# 7segement4digits1badidea-max7219-smd-mk-.net
KiCad netlist of a schematic drawn in EAGLE
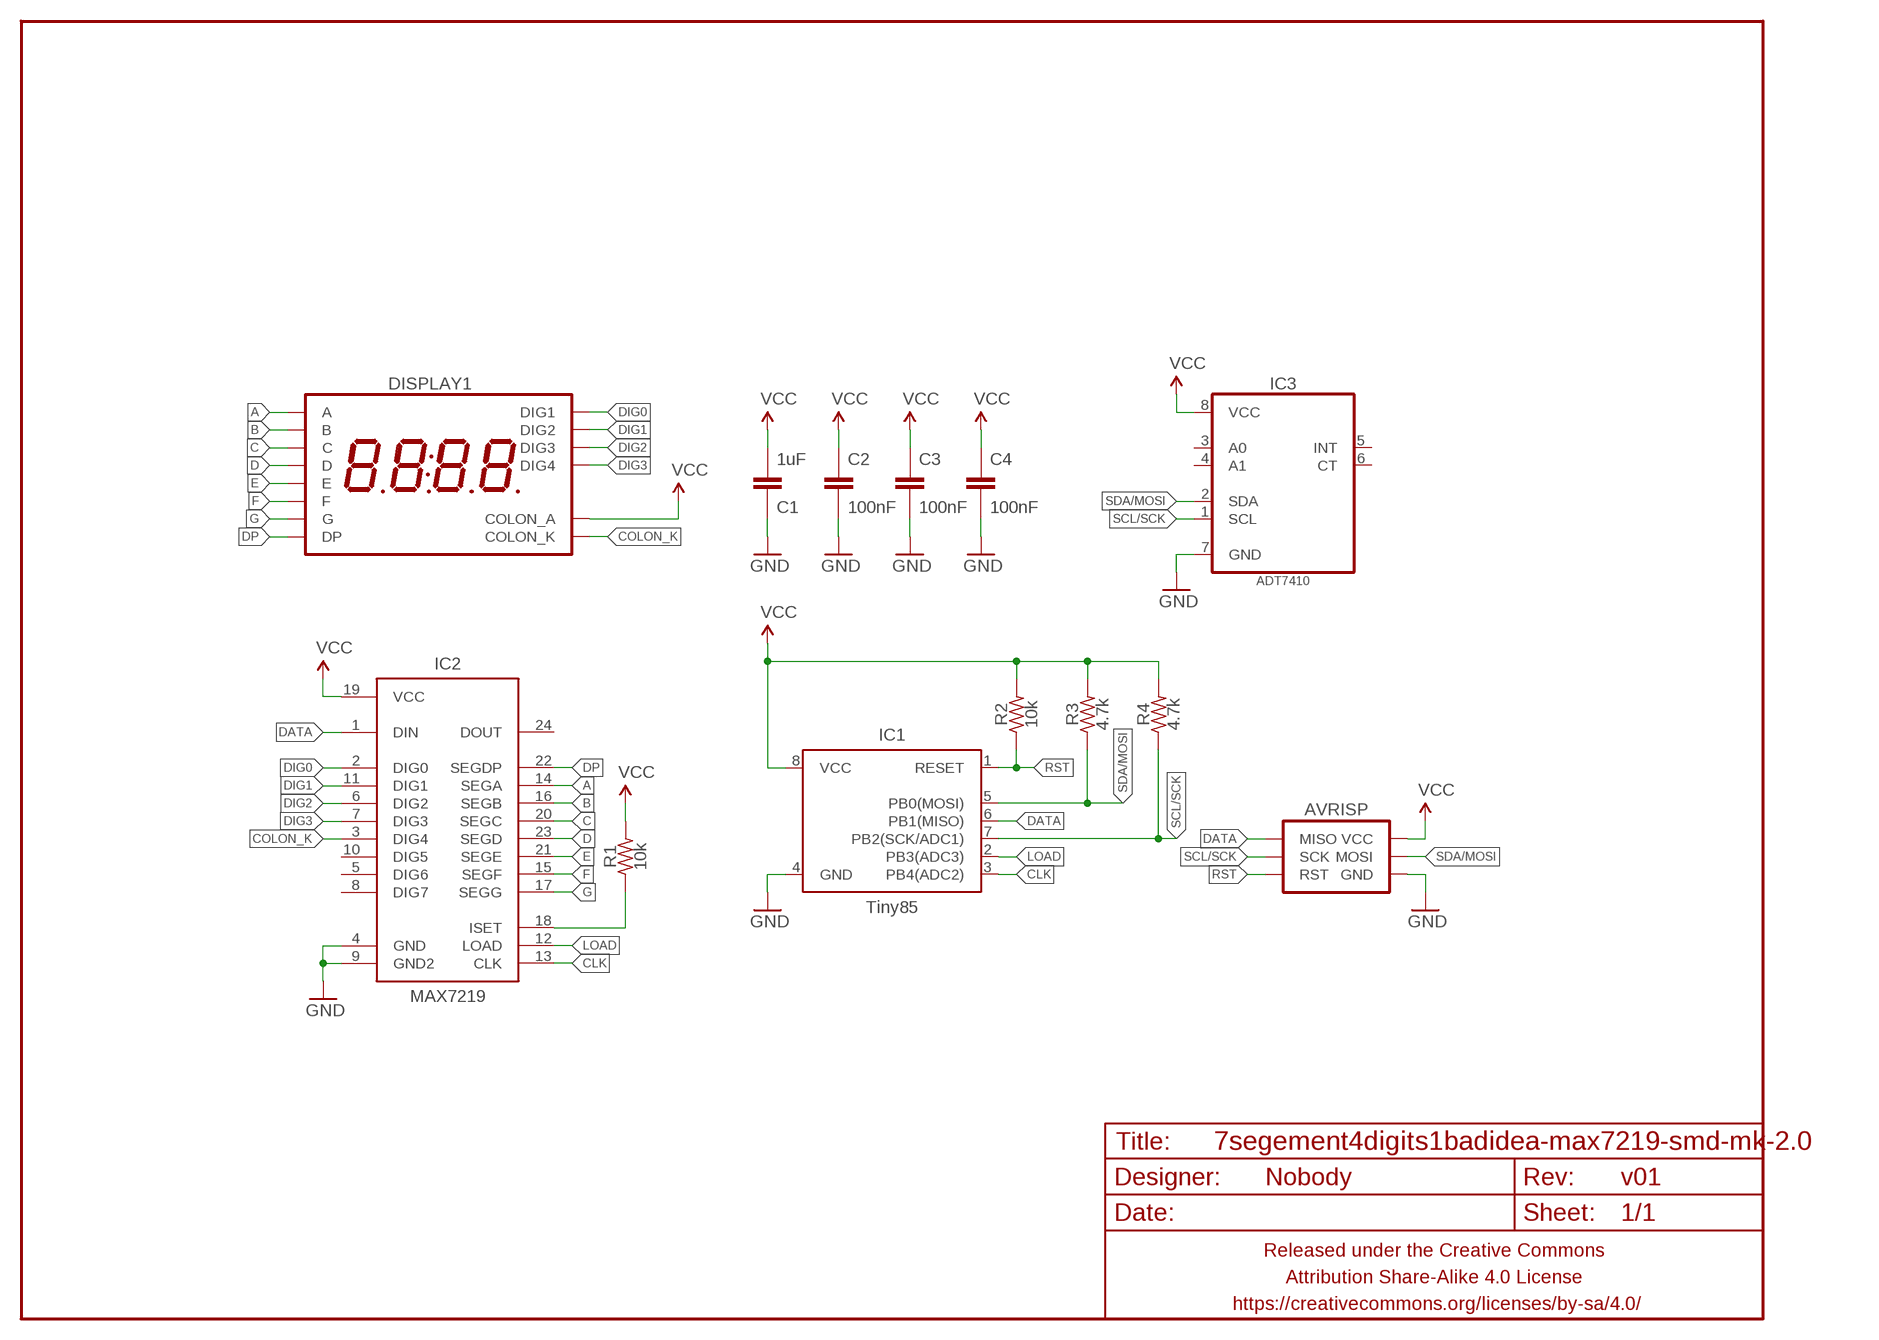
[diagram p0: schematic, sheet 1]

(export (version "E")
  (design (tool "Eeschema 10.0.6"))
  (components
    (comp (ref "AVRISP")
      (value "AVR_SPI_PRG_6PTH")
      (footprint "eagle-import:2X3")
      (libsource (lib "eagle-import") (part "AVR_SPI_PRG_6PTH"))
    )
    (comp (ref "C1")
      (value "1uF")
      (footprint "eagle-import:C0805")
      (libsource (lib "eagle-import") (part "CAPACITOR-CERAMICC0805"))
    )
    (comp (ref "C2")
      (value "100nF")
      (footprint "eagle-import:C0805")
      (libsource (lib "eagle-import") (part "CAPACITOR-CERAMICC0805"))
    )
    (comp (ref "C3")
      (value "100nF")
      (footprint "eagle-import:C0805")
      (libsource (lib "eagle-import") (part "CAPACITOR-CERAMICC0805"))
    )
    (comp (ref "C4")
      (value "100nF")
      (footprint "eagle-import:C0805")
      (libsource (lib "eagle-import") (part "CAPACITOR-CERAMICC0805"))
    )
    (comp (ref "DISPLAY1")
      (value "7SEG_4DIGIT_COLONADAFRUIT_0.56IN")
      (footprint "eagle-import:7SEG_4DIG")
      (libsource (lib "eagle-import") (part "7SEG_4DIGIT_COLONADAFRUIT_0.56IN"))
    )
    (comp (ref "FRAME1")
      (value "FRAME-LETTERNO_PACKAGE")
      (footprint "eagle-import:DUMMY")
      (fields (field (name "DESIGNER") "Nobody"))
      (libsource (lib "eagle-import") (part "FRAME-LETTERNO_PACKAGE"))
    )
    (comp (ref "IC1")
      (value "Tiny85")
      (footprint "eagle-import:SO08-EIAJ")
      (libsource (lib "eagle-import") (part "ATTINY45TINY85-20-SOICW"))
    )
    (comp (ref "IC2")
      (value "MAX7219")
      (footprint "eagle-import:SO24W")
      (libsource (lib "eagle-import") (part "MAX7219SOIC-W"))
    )
    (comp (ref "IC3")
      (value "ADT7410")
      (footprint "eagle-import:SOIC127P600X175-8N")
      (fields (field (name "MPN") "ADT7410TRZ"))
      (libsource (lib "eagle-import") (part "ADT7410TRZSOIC8N"))
    )
    (comp (ref "R1")
      (value "10k")
      (footprint "eagle-import:R0805")
      (libsource (lib "eagle-import") (part "RESISTORR0805"))
    )
    (comp (ref "R2")
      (value "10k")
      (footprint "eagle-import:R0805")
      (libsource (lib "eagle-import") (part "RESISTORR0805"))
    )
    (comp (ref "R3")
      (value "4.7k")
      (footprint "eagle-import:R0805")
      (libsource (lib "eagle-import") (part "RESISTORR0805"))
    )
    (comp (ref "R4")
      (value "4.7k")
      (footprint "eagle-import:R0805")
      (libsource (lib "eagle-import") (part "RESISTORR0805"))
    )
  )
  (nets
    (net (code "1") (name "A") (class "Default")
      (node (ref "DISPLAY1") (pin "P$13") (pinfunction "A_P$13") (pintype "passive"))
      (node (ref "IC2") (pin "14") (pinfunction "SEGA_14") (pintype "bidirectional"))
    )
    (net (code "2") (name "B") (class "Default")
      (node (ref "DISPLAY1") (pin "P$9") (pinfunction "B_P$9") (pintype "passive"))
      (node (ref "IC2") (pin "16") (pinfunction "SEGB_16") (pintype "bidirectional"))
    )
    (net (code "3") (name "C") (class "Default")
      (node (ref "DISPLAY1") (pin "P$4") (pinfunction "C_P$4") (pintype "passive"))
      (node (ref "IC2") (pin "20") (pinfunction "SEGC_20") (pintype "bidirectional"))
    )
    (net (code "4") (name "CLK") (class "Default")
      (node (ref "IC1") (pin "3") (pinfunction "PB4(ADC2)_3") (pintype "bidirectional"))
      (node (ref "IC2") (pin "13") (pinfunction "CLK_13") (pintype "bidirectional"))
    )
    (net (code "5") (name "COLON_K") (class "Default")
      (node (ref "DISPLAY1") (pin "P$7") (pinfunction "COLON_K_P$7") (pintype "passive"))
      (node (ref "IC2") (pin "3") (pinfunction "DIG4_3") (pintype "bidirectional"))
    )
    (net (code "6") (name "D") (class "Default")
      (node (ref "DISPLAY1") (pin "P$2") (pinfunction "D_P$2") (pintype "passive"))
      (node (ref "IC2") (pin "23") (pinfunction "SEGD_23") (pintype "bidirectional"))
    )
    (net (code "7") (name "DATA") (class "Default")
      (node (ref "AVRISP") (pin "1") (pinfunction "MISO_1") (pintype "passive"))
      (node (ref "IC1") (pin "6") (pinfunction "PB1(MISO)_6") (pintype "bidirectional"))
      (node (ref "IC2") (pin "1") (pinfunction "DIN_1") (pintype "bidirectional"))
    )
    (net (code "8") (name "DIG0") (class "Default")
      (node (ref "DISPLAY1") (pin "P$14") (pinfunction "DIG1_P$14") (pintype "passive"))
      (node (ref "IC2") (pin "2") (pinfunction "DIG0_2") (pintype "bidirectional"))
    )
    (net (code "9") (name "DIG1") (class "Default")
      (node (ref "DISPLAY1") (pin "P$11") (pinfunction "DIG2_P$11") (pintype "passive"))
      (node (ref "IC2") (pin "11") (pinfunction "DIG1_11") (pintype "bidirectional"))
    )
    (net (code "10") (name "DIG2") (class "Default")
      (node (ref "DISPLAY1") (pin "P$10") (pinfunction "DIG3_P$10") (pintype "passive"))
      (node (ref "IC2") (pin "6") (pinfunction "DIG2_6") (pintype "bidirectional"))
    )
    (net (code "11") (name "DIG3") (class "Default")
      (node (ref "DISPLAY1") (pin "P$6") (pinfunction "DIG4_P$6") (pintype "passive"))
      (node (ref "IC2") (pin "7") (pinfunction "DIG3_7") (pintype "bidirectional"))
    )
    (net (code "12") (name "DP") (class "Default")
      (node (ref "DISPLAY1") (pin "P$3") (pinfunction "DP_P$3") (pintype "passive"))
      (node (ref "IC2") (pin "22") (pinfunction "SEGDP_22") (pintype "bidirectional"))
    )
    (net (code "13") (name "E") (class "Default")
      (node (ref "DISPLAY1") (pin "P$1") (pinfunction "E_P$1") (pintype "passive"))
      (node (ref "IC2") (pin "21") (pinfunction "SEGE_21") (pintype "bidirectional"))
    )
    (net (code "14") (name "F") (class "Default")
      (node (ref "DISPLAY1") (pin "P$12") (pinfunction "F_P$12") (pintype "passive"))
      (node (ref "IC2") (pin "15") (pinfunction "SEGF_15") (pintype "bidirectional"))
    )
    (net (code "15") (name "G") (class "Default")
      (node (ref "DISPLAY1") (pin "P$5") (pinfunction "G_P$5") (pintype "passive"))
      (node (ref "IC2") (pin "17") (pinfunction "SEGG_17") (pintype "bidirectional"))
    )
    (net (code "16") (name "GND") (class "Default")
      (node (ref "AVRISP") (pin "6") (pinfunction "GND_6") (pintype "passive"))
      (node (ref "C1") (pin "1") (pinfunction "1_1") (pintype "passive"))
      (node (ref "C2") (pin "2") (pinfunction "2_2") (pintype "passive"))
      (node (ref "C3") (pin "2") (pinfunction "2_2") (pintype "passive"))
      (node (ref "C4") (pin "2") (pinfunction "2_2") (pintype "passive"))
      (node (ref "IC1") (pin "4") (pinfunction "GND_4") (pintype "bidirectional"))
      (node (ref "IC2") (pin "4") (pinfunction "GND_4") (pintype "bidirectional"))
      (node (ref "IC2") (pin "9") (pinfunction "GND2_9") (pintype "bidirectional"))
      (node (ref "IC3") (pin "7") (pinfunction "GND_7") (pintype "passive"))
    )
    (net (code "17") (name "LOAD") (class "Default")
      (node (ref "IC1") (pin "2") (pinfunction "PB3(ADC3)_2") (pintype "bidirectional"))
      (node (ref "IC2") (pin "12") (pinfunction "LOAD_12") (pintype "bidirectional"))
    )
    (net (code "18") (name "Net-(IC2-ISET)") (class "Default")
      (node (ref "IC2") (pin "18") (pinfunction "ISET_18") (pintype "bidirectional"))
      (node (ref "R1") (pin "1") (pinfunction "1_1") (pintype "passive"))
    )
    (net (code "19") (name "RST") (class "Default")
      (node (ref "AVRISP") (pin "5") (pinfunction "RST_5") (pintype "passive"))
      (node (ref "IC1") (pin "1") (pinfunction "RESET_1") (pintype "bidirectional"))
      (node (ref "R2") (pin "1") (pinfunction "1_1") (pintype "passive"))
    )
    (net (code "20") (name "SCL{slash}SCK") (class "Default")
      (node (ref "AVRISP") (pin "3") (pinfunction "SCK_3") (pintype "passive"))
      (node (ref "IC1") (pin "7") (pinfunction "PB2(SCK/ADC1)_7") (pintype "bidirectional"))
      (node (ref "IC3") (pin "1") (pinfunction "SCL_1") (pintype "input"))
      (node (ref "R4") (pin "1") (pinfunction "1_1") (pintype "passive"))
    )
    (net (code "21") (name "SDA{slash}MOSI") (class "Default")
      (node (ref "AVRISP") (pin "4") (pinfunction "MOSI_4") (pintype "passive"))
      (node (ref "IC1") (pin "5") (pinfunction "PB0(MOSI)_5") (pintype "bidirectional"))
      (node (ref "IC3") (pin "2") (pinfunction "SDA_2") (pintype "bidirectional"))
      (node (ref "R3") (pin "1") (pinfunction "1_1") (pintype "passive"))
    )
    (net (code "22") (name "VCC") (class "Default")
      (node (ref "AVRISP") (pin "2") (pinfunction "VCC_2") (pintype "passive"))
      (node (ref "C1") (pin "2") (pinfunction "2_2") (pintype "passive"))
      (node (ref "C2") (pin "1") (pinfunction "1_1") (pintype "passive"))
      (node (ref "C3") (pin "1") (pinfunction "1_1") (pintype "passive"))
      (node (ref "C4") (pin "1") (pinfunction "1_1") (pintype "passive"))
      (node (ref "DISPLAY1") (pin "P$8") (pinfunction "COLON_A_P$8") (pintype "passive"))
      (node (ref "IC1") (pin "8") (pinfunction "VCC_8") (pintype "bidirectional"))
      (node (ref "IC2") (pin "19") (pinfunction "VCC_19") (pintype "bidirectional"))
      (node (ref "IC3") (pin "8") (pinfunction "VCC_8") (pintype "power_in"))
      (node (ref "R1") (pin "2") (pinfunction "2_2") (pintype "passive"))
      (node (ref "R2") (pin "2") (pinfunction "2_2") (pintype "passive"))
      (node (ref "R3") (pin "2") (pinfunction "2_2") (pintype "passive"))
      (node (ref "R4") (pin "2") (pinfunction "2_2") (pintype "passive"))
    )
    (net (code "23") (name "unconnected-(IC2-DIG5-Pad10)") (class "Default")
      (node (ref "IC2") (pin "10") (pinfunction "DIG5_10") (pintype "bidirectional"))
    )
    (net (code "24") (name "unconnected-(IC2-DIG6-Pad5)") (class "Default")
      (node (ref "IC2") (pin "5") (pinfunction "DIG6_5") (pintype "bidirectional"))
    )
    (net (code "25") (name "unconnected-(IC2-DIG7-Pad8)") (class "Default")
      (node (ref "IC2") (pin "8") (pinfunction "DIG7_8") (pintype "bidirectional"))
    )
    (net (code "26") (name "unconnected-(IC2-DOUT-Pad24)") (class "Default")
      (node (ref "IC2") (pin "24") (pinfunction "DOUT_24") (pintype "bidirectional"))
    )
    (net (code "27") (name "unconnected-(IC3-A0-Pad3)") (class "Default")
      (node (ref "IC3") (pin "3") (pinfunction "A0_3") (pintype "input"))
    )
    (net (code "28") (name "unconnected-(IC3-A1-Pad4)") (class "Default")
      (node (ref "IC3") (pin "4") (pinfunction "A1_4") (pintype "input"))
    )
    (net (code "29") (name "unconnected-(IC3-CT-Pad6)") (class "Default")
      (node (ref "IC3") (pin "6") (pinfunction "CT_6") (pintype "output"))
    )
    (net (code "30") (name "unconnected-(IC3-INT-Pad5)") (class "Default")
      (node (ref "IC3") (pin "5") (pinfunction "INT_5") (pintype "output"))
    )
  )
)
